# Gyro.net
KiCad netlist of a schematic drawn in Altium Designer
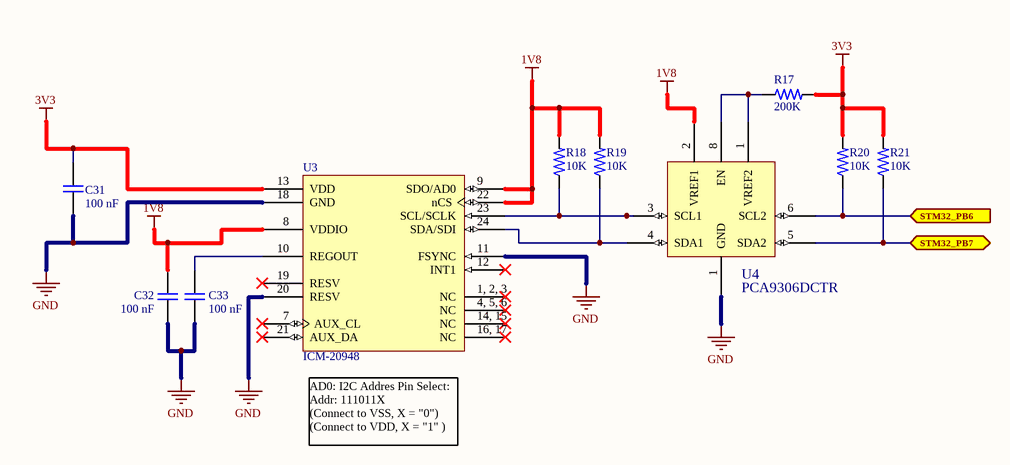
[diagram p0: Gyro.SchDoc]

(export (version "E")
  (design (tool "Eeschema 10.0.6"))
  (components
    (comp (ref "C31")
      (value "100 nF")
      (footprint "MergenElektronik_Capacitors_Ceramics_SMDs_0603_M_NS")
      (description "Mergen Elektronik - Capacitors - Ceramics - SMDs - 0603 - 100 nF - 100V")
      (fields (field (name "MANUFACTURER") "Samsung Electro-Mechanics") (field (name "TOLERANCE") "±10%"))
      (libsource (lib "MergenElektronik_Capacitors_Ceramics_SMDs") (part "MergenElektronik_Capacitors_Ceramic_SMDs_100nF_100V"))
    )
    (comp (ref "C32")
      (value "100 nF")
      (footprint "MergenElektronik_Capacitors_Ceramics_SMDs_0603_M_NS")
      (description "Mergen Elektronik - Capacitors - Ceramics - SMDs - 0603 - 100 nF - 100V")
      (fields (field (name "MANUFACTURER") "Samsung Electro-Mechanics") (field (name "TOLERANCE") "±10%"))
      (libsource (lib "MergenElektronik_Capacitors_Ceramics_SMDs") (part "MergenElektronik_Capacitors_Ceramic_SMDs_100nF_100V"))
    )
    (comp (ref "C33")
      (value "100 nF")
      (footprint "MergenElektronik_Capacitors_Ceramics_SMDs_0603_M_NS")
      (description "Mergen Elektronik - Capacitors - Ceramics - SMDs - 0603 - 100 nF - 100V")
      (fields (field (name "MANUFACTURER") "Samsung Electro-Mechanics") (field (name "TOLERANCE") "±10%"))
      (libsource (lib "MergenElektronik_Capacitors_Ceramics_SMDs") (part "MergenElektronik_Capacitors_Ceramic_SMDs_100nF_100V"))
    )
    (comp (ref "R17")
      (value "200K")
      (footprint "MergenElektronik_Resistors_ChipResistors_0603_M_NS")
      (description "Mergen Elektronik - Resistors - Chip Resistors - 0603 - 200K")
      (fields (field (name "MANUFACTURER") "Stackpole Electronics Inc") (field (name "POWER") "1/10W"))
      (libsource (lib "MergenElektronik_Resistors_ChipResistors") (part "MergenElektronik_Resistors_ChipResistors_0603_200K"))
    )
    (comp (ref "R18")
      (value "10K")
      (footprint "MergenElektronik_Resistors_ChipResistors_0603_M_NS")
      (description "Mergen Elektronik - Resistors - Chip Resistors - 0603 - 10K")
      (fields (field (name "MANUFACTURER") "Stackpole Electronics Inc") (field (name "POWER") "1/10W"))
      (libsource (lib "MergenElektronik_Resistors_ChipResistors") (part "MergenElektronik_Resistors_ChipResistors_0603_10K"))
    )
    (comp (ref "R19")
      (value "10K")
      (footprint "MergenElektronik_Resistors_ChipResistors_0603_M_NS")
      (description "Mergen Elektronik - Resistors - Chip Resistors - 0603 - 10K")
      (fields (field (name "MANUFACTURER") "Stackpole Electronics Inc") (field (name "POWER") "1/10W"))
      (libsource (lib "MergenElektronik_Resistors_ChipResistors") (part "MergenElektronik_Resistors_ChipResistors_0603_10K"))
    )
    (comp (ref "R20")
      (value "10K")
      (footprint "MergenElektronik_Resistors_ChipResistors_0603_M_NS")
      (description "Mergen Elektronik - Resistors - Chip Resistors - 0603 - 10K")
      (fields (field (name "MANUFACTURER") "Stackpole Electronics Inc") (field (name "POWER") "1/10W"))
      (libsource (lib "MergenElektronik_Resistors_ChipResistors") (part "MergenElektronik_Resistors_ChipResistors_0603_10K"))
    )
    (comp (ref "R21")
      (value "10K")
      (footprint "MergenElektronik_Resistors_ChipResistors_0603_M_NS")
      (description "Mergen Elektronik - Resistors - Chip Resistors - 0603 - 10K")
      (fields (field (name "MANUFACTURER") "Stackpole Electronics Inc") (field (name "POWER") "1/10W"))
      (libsource (lib "MergenElektronik_Resistors_ChipResistors") (part "MergenElektronik_Resistors_ChipResistors_0603_10K"))
    )
    (comp (ref "U3")
      (value "ICM-20948")
      (footprint "MergenElektronik_Sensors_Gyroscope-Accelerometer-Magnetometer_24-QFN")
      (description "Mergen Elektronik - Sensors - Gytoscope - Accelometer - Magnetometer - ICM-20948")
      (fields (field (name "MANUFACTURER") "TDK InvenSense"))
      (libsource (lib "MergenElektronik_Sensors_Gyroscope-Accelerometer-Magnetometer") (part "MergenElektronik_Sensors_Gyroscope-Accelerometer-Magnetometer_ICM-20948"))
    )
    (comp (ref "U4")
      (value "PCA9306DCTR")
      (footprint "MergenElektronik_Logics_LevelShifters_SSOP-8")
      (description "Mergen Elektronik - Logics - Level Shifters - PCA9306DCTR")
      (fields (field (name "MANUFACTURER") "Texas Instruments"))
      (libsource (lib "MergenElektronik_Logics_LevelShifters") (part "MergenElektronik_Logics_LevelShifters_PCA9306DCTR"))
    )
  )
  (nets
    (net (code "1") (name "/STM32_PB6") (class "Default")
      (node (ref "R20") (pin "1") (pinfunction "1_1") (pintype "passive"))
      (node (ref "U4") (pin "6") (pinfunction "SCL2_6") (pintype "bidirectional"))
    )
    (net (code "2") (name "/STM32_PB7") (class "Default")
      (node (ref "R21") (pin "1") (pinfunction "1_1") (pintype "passive"))
      (node (ref "U4") (pin "5") (pinfunction "SDA2_5") (pintype "bidirectional"))
    )
    (net (code "3") (name "1V8") (class "Default")
      (node (ref "C32") (pin "1") (pinfunction "1_1") (pintype "passive"))
      (node (ref "R18") (pin "2") (pinfunction "2_2") (pintype "passive"))
      (node (ref "R19") (pin "2") (pinfunction "2_2") (pintype "passive"))
      (node (ref "U3") (pin "22") (pinfunction "nCS_22") (pintype "bidirectional"))
      (node (ref "U3") (pin "8") (pinfunction "VDDIO_8") (pintype "power_in"))
      (node (ref "U3") (pin "9") (pinfunction "SDO/AD0_9") (pintype "bidirectional"))
      (node (ref "U4") (pin "2") (pinfunction "VREF1_2") (pintype "power_in"))
    )
    (net (code "4") (name "3V3") (class "Default")
      (node (ref "C31") (pin "1") (pinfunction "1_1") (pintype "passive"))
      (node (ref "R17") (pin "2") (pinfunction "2_2") (pintype "passive"))
      (node (ref "R20") (pin "2") (pinfunction "2_2") (pintype "passive"))
      (node (ref "R21") (pin "2") (pinfunction "2_2") (pintype "passive"))
      (node (ref "U3") (pin "13") (pinfunction "VDD_13") (pintype "power_in"))
    )
    (net (code "5") (name "GND") (class "Default")
      (node (ref "C31") (pin "2") (pinfunction "2_2") (pintype "passive"))
      (node (ref "C32") (pin "2") (pinfunction "2_2") (pintype "passive"))
      (node (ref "C33") (pin "2") (pinfunction "2_2") (pintype "passive"))
      (node (ref "U3") (pin "11") (pinfunction "FSYNC_11") (pintype "input"))
      (node (ref "U3") (pin "18") (pinfunction "GND_18") (pintype "power_in"))
      (node (ref "U3") (pin "20") (pinfunction "RESV_20") (pintype "passive"))
      (node (ref "U4") (pin "1") (pinfunction "GND_1") (pintype "power_in"))
    )
    (net (code "6") (name "Net-(U3-REGOUT)") (class "Default")
      (node (ref "C33") (pin "1") (pinfunction "1_1") (pintype "passive"))
      (node (ref "U3") (pin "10") (pinfunction "REGOUT_10") (pintype "power_in"))
    )
    (net (code "7") (name "Net-(U3-SCL{slash}SCLK)") (class "Default")
      (node (ref "R18") (pin "1") (pinfunction "1_1") (pintype "passive"))
      (node (ref "U3") (pin "23") (pinfunction "SCL/SCLK_23") (pintype "input"))
      (node (ref "U4") (pin "3") (pinfunction "SCL1_3") (pintype "bidirectional"))
    )
    (net (code "8") (name "Net-(U3-SDA{slash}SDI)") (class "Default")
      (node (ref "R19") (pin "1") (pinfunction "1_1") (pintype "passive"))
      (node (ref "U3") (pin "24") (pinfunction "SDA/SDI_24") (pintype "bidirectional"))
      (node (ref "U4") (pin "4") (pinfunction "SDA1_4") (pintype "bidirectional"))
    )
    (net (code "9") (name "Net-(U4-EN)") (class "Default")
      (node (ref "R17") (pin "1") (pinfunction "1_1") (pintype "passive"))
      (node (ref "U4") (pin "1") (pinfunction "VREF2_1") (pintype "power_in"))
      (node (ref "U4") (pin "8") (pinfunction "EN_8") (pintype "passive"))
    )
    (net (code "10") (name "unconnected-(U3-AUX_CL-Pad7)") (class "Default")
      (node (ref "U3") (pin "7") (pinfunction "AUX_CL_7") (pintype "bidirectional+no_connect"))
    )
    (net (code "11") (name "unconnected-(U3-AUX_DA-Pad21)") (class "Default")
      (node (ref "U3") (pin "21") (pinfunction "AUX_DA_21") (pintype "bidirectional+no_connect"))
    )
    (net (code "12") (name "unconnected-(U3-INT1-Pad12)") (class "Default")
      (node (ref "U3") (pin "12") (pinfunction "INT1_12") (pintype "input+no_connect"))
    )
    (net (code "13") (name "unconnected-(U3-NC-Pad1)") (class "Default")
      (node (ref "U3") (pin "1") (pinfunction "NC_1") (pintype "passive+no_connect"))
      (node (ref "U3") (pin "2") (pinfunction "NC_2") (pintype "passive+no_connect"))
      (node (ref "U3") (pin "3") (pinfunction "NC_3") (pintype "passive+no_connect"))
    )
    (net (code "14") (name "unconnected-(U3-NC-Pad4)") (class "Default")
      (node (ref "U3") (pin "4") (pinfunction "NC_4") (pintype "passive+no_connect"))
      (node (ref "U3") (pin "5") (pinfunction "NC_5") (pintype "passive+no_connect"))
      (node (ref "U3") (pin "6") (pinfunction "NC_6") (pintype "passive+no_connect"))
    )
    (net (code "15") (name "unconnected-(U3-NC-Pad14)") (class "Default")
      (node (ref "U3") (pin "14") (pinfunction "NC_14") (pintype "passive+no_connect"))
      (node (ref "U3") (pin "15") (pinfunction "NC_15") (pintype "passive+no_connect"))
    )
    (net (code "16") (name "unconnected-(U3-NC-Pad16)") (class "Default")
      (node (ref "U3") (pin "16") (pinfunction "NC_16") (pintype "passive+no_connect"))
      (node (ref "U3") (pin "17") (pinfunction "NC_17") (pintype "passive+no_connect"))
    )
    (net (code "17") (name "unconnected-(U3-RESV-Pad19)") (class "Default")
      (node (ref "U3") (pin "19") (pinfunction "RESV_19") (pintype "passive+no_connect"))
    )
  )
)
